# 1-Schematic_New_Project.net
KiCad netlist of a schematic drawn in EasyEDA
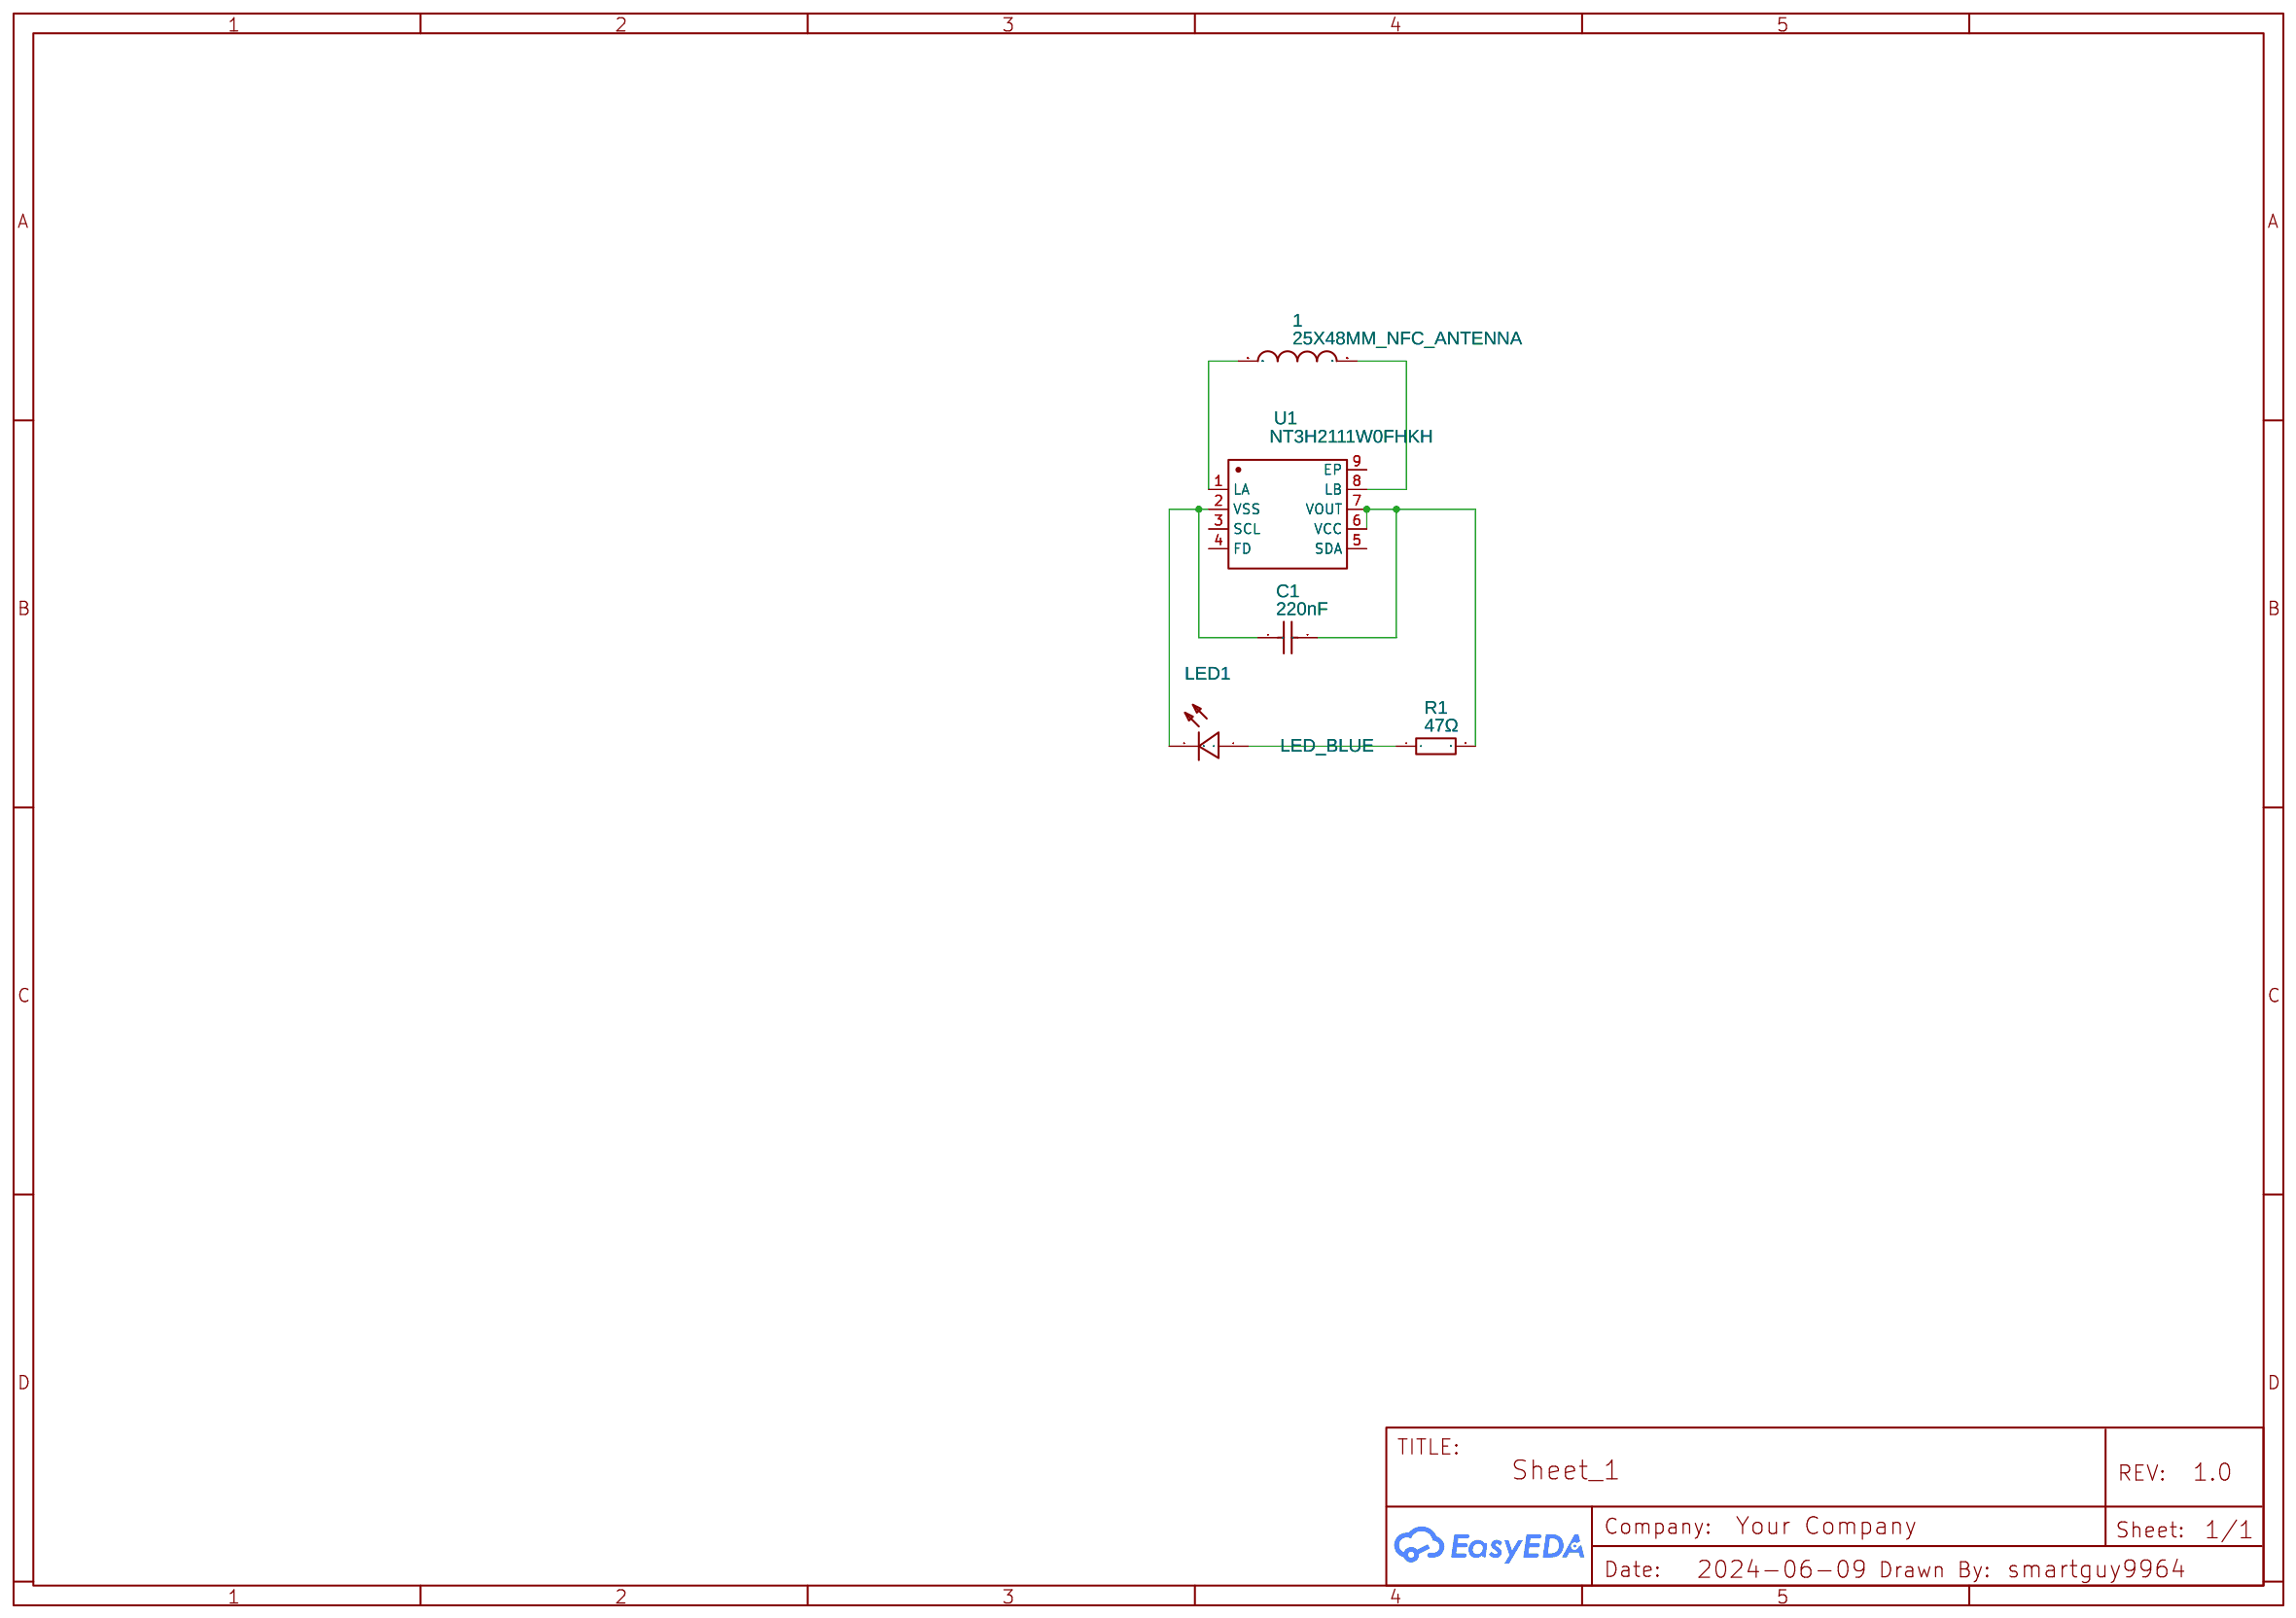
[diagram p0: schematic sheet]

(export (version "E")
  (design (tool "Eeschema 10.0.6"))
  (components
    (comp (ref "1") (value "25X48MM_NFC_ANTENNA") (libsource (lib "") (part "25X48MM_NFC_ANTENNA")))
    (comp (ref "C1")
      (value "220nF")
      (fields
        (field (name "Manufacturer Part") "CL10B224KA8NNNC")
        (field (name "Manufacturer") "SAMSUNG(三星)")
      )
      (libsource (lib "") (part "CL10B224KA8NNNC"))
    )
    (comp (ref "LED1") (value "LED_BLUE") (libsource (lib "") (part "LED_BLUE")))
    (comp (ref "R1")
      (value "47Ω")
      (fields
        (field (name "Manufacturer Part") "0603WAF470JT5E")
        (field (name "Manufacturer") "UNI-ROYAL(厚声)")
      )
      (libsource (lib "") (part "0603WAF470JT5E"))
    )
    (comp (ref "U1")
      (value "NT3H2111W0FHKH")
      (fields (field (name "Manufacturer") "NXP(恩智浦)"))
      (libsource (lib "") (part "NT3H2111W0FHKH"))
    )
  )
  (nets
    (net (code "1") (name "Net-(LED1-Pad1)") (class "Default")
      (node (ref "LED1") (pin "1") (pinfunction "1_1") (pintype "unspecified"))
      (node (ref "R1") (pin "1") (pinfunction "1_1") (pintype "input"))
    )
    (net (code "2") (name "Net-(U1-LA)") (class "Default")
      (node (ref "1") (pin "P$1") (pinfunction "P$1_P$1") (pintype "bidirectional"))
      (node (ref "U1") (pin "1") (pinfunction "LA_1") (pintype "unspecified"))
    )
    (net (code "3") (name "Net-(U1-LB)") (class "Default")
      (node (ref "1") (pin "P$2") (pinfunction "P$2_P$2") (pintype "bidirectional"))
      (node (ref "U1") (pin "8") (pinfunction "LB_8") (pintype "unspecified"))
    )
    (net (code "4") (name "Net-(U1-VCC)") (class "Default")
      (node (ref "C1") (pin "2") (pinfunction "2_2") (pintype "input"))
      (node (ref "R1") (pin "2") (pinfunction "2_2") (pintype "input"))
      (node (ref "U1") (pin "6") (pinfunction "VCC_6") (pintype "unspecified"))
      (node (ref "U1") (pin "7") (pinfunction "VOUT_7") (pintype "unspecified"))
    )
    (net (code "5") (name "Net-(U1-VSS)") (class "Default")
      (node (ref "C1") (pin "1") (pinfunction "1_1") (pintype "input"))
      (node (ref "LED1") (pin "2") (pinfunction "2_2") (pintype "unspecified"))
      (node (ref "U1") (pin "2") (pinfunction "VSS_2") (pintype "unspecified"))
    )
    (net (code "6") (name "unconnected-(U1-EP-Pad9)") (class "Default")
      (node (ref "U1") (pin "9") (pinfunction "EP_9") (pintype "unspecified"))
    )
    (net (code "7") (name "unconnected-(U1-FD-Pad4)") (class "Default")
      (node (ref "U1") (pin "4") (pinfunction "FD_4") (pintype "unspecified"))
    )
    (net (code "8") (name "unconnected-(U1-SCL-Pad3)") (class "Default")
      (node (ref "U1") (pin "3") (pinfunction "SCL_3") (pintype "unspecified"))
    )
    (net (code "9") (name "unconnected-(U1-SDA-Pad5)") (class "Default")
      (node (ref "U1") (pin "5") (pinfunction "SDA_5") (pintype "unspecified"))
    )
  )
)
